# TFTBR.net
KiCad netlist of a schematic drawn in EAGLE
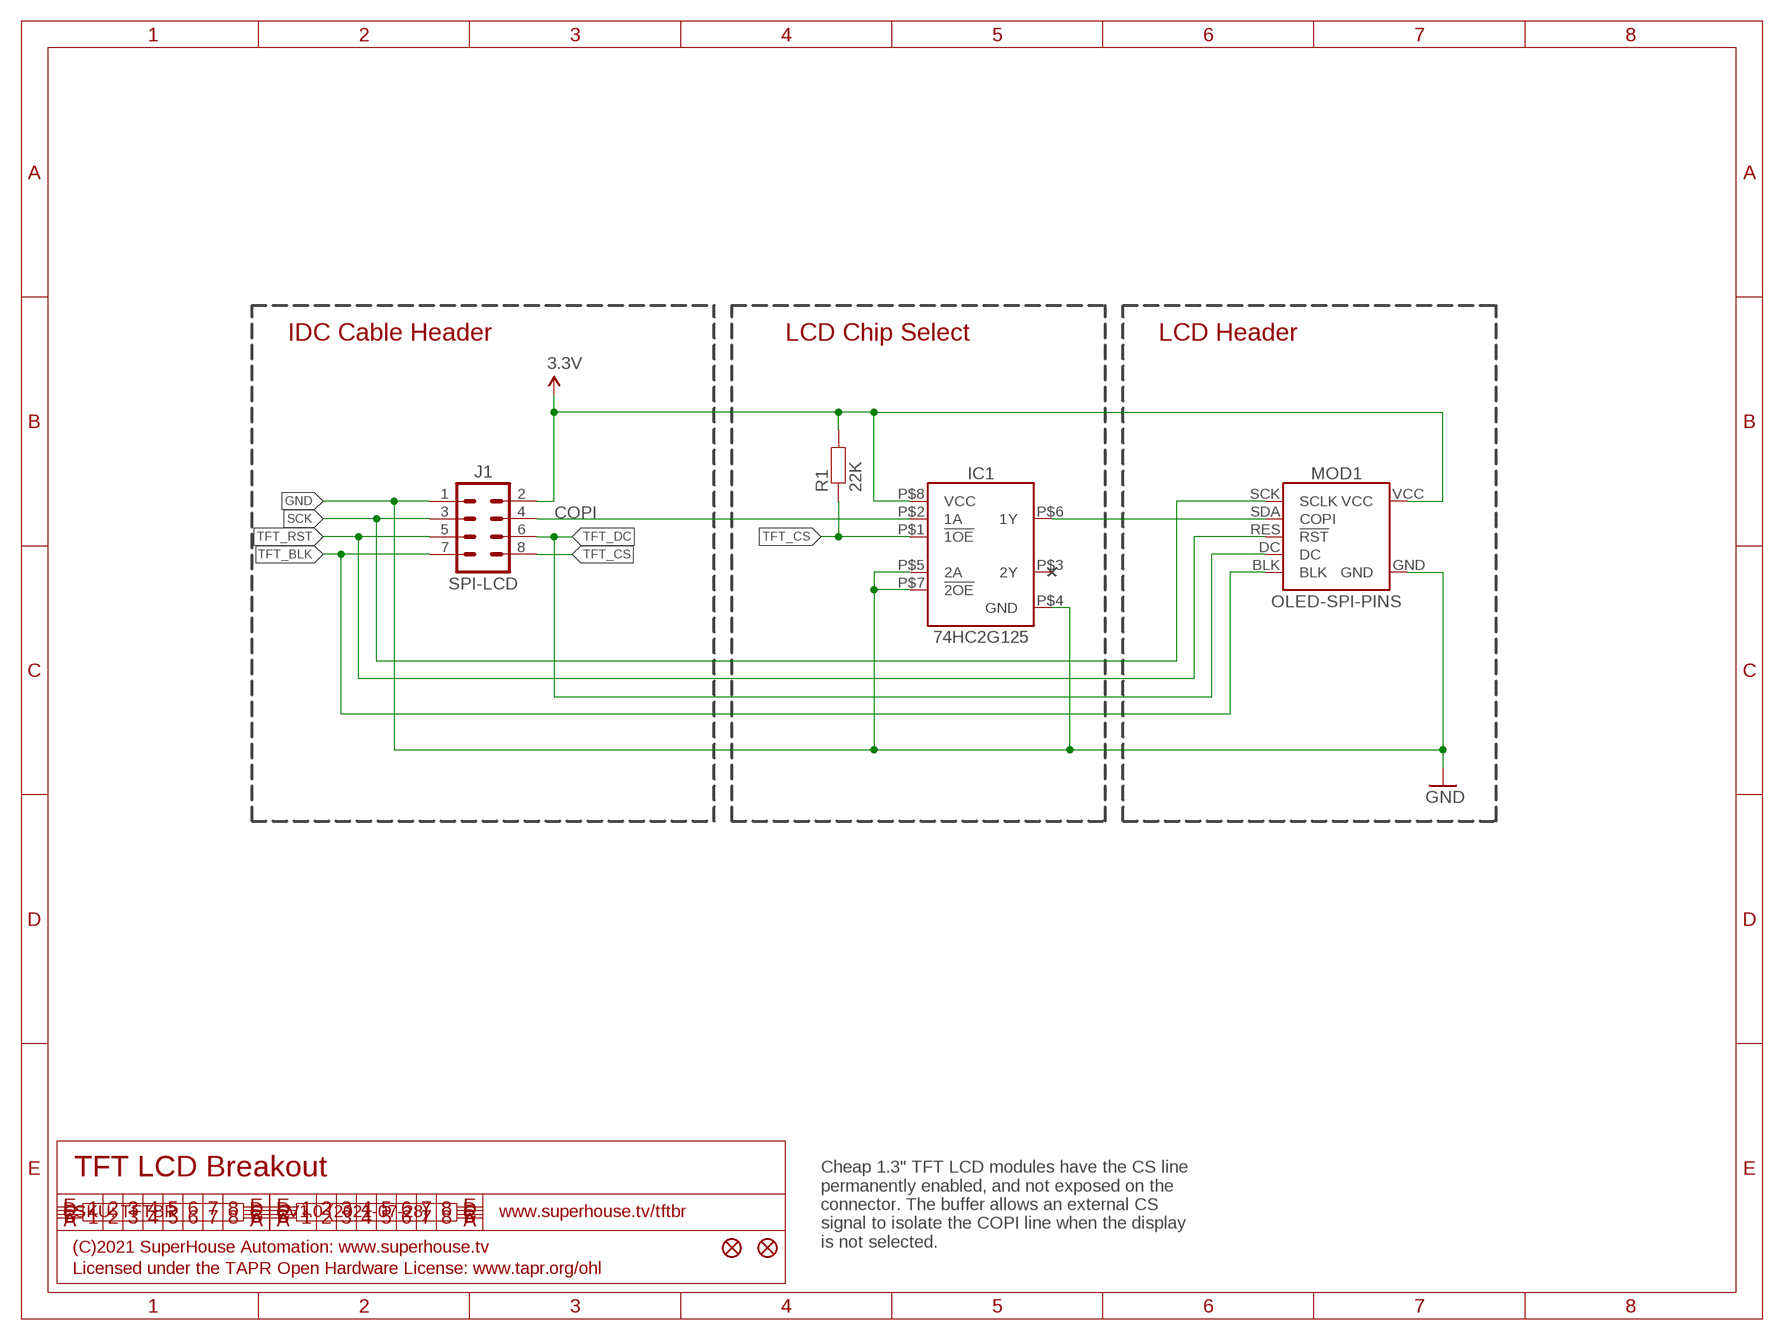
[diagram p0: schematic, sheet 1]

(export (version "E")
  (design (tool "Eeschema 10.0.6"))
  (components
    (comp (ref "FID1")
      (value "FIDUCIAL1X2.5")
      (footprint "eagle-import:FIDUCIAL-1X2.5")
      (libsource (lib "eagle-import") (part "FIDUCIAL1X2.5"))
    )
    (comp (ref "FID2")
      (value "FIDUCIAL1X2.5")
      (footprint "eagle-import:FIDUCIAL-1X2.5")
      (libsource (lib "eagle-import") (part "FIDUCIAL1X2.5"))
    )
    (comp (ref "IC1")
      (value "74HC2G125")
      (footprint "eagle-import:74HC2G125")
      (libsource (lib "eagle-import") (part "74HC2G125-TSSOP8"))
    )
    (comp (ref "J1")
      (value "SPI-LCD")
      (footprint "eagle-import:2X04-2.54-SHROUDED")
      (libsource (lib "eagle-import") (part "M02X4-SHROUD"))
    )
    (comp (ref "MOD1")
      (value "OLED-SPI-PINS")
      (footprint "eagle-import:OLED-240X240-1.3")
      (libsource (lib "eagle-import") (part "OLED-SPI-PINS"))
    )
    (comp (ref "R1")
      (value "22K")
      (footprint "eagle-import:R0603")
      (libsource (lib "eagle-import") (part "RESISTOR0603"))
    )
  )
  (nets
    (net (code "1") (name "/COPI") (class "Default")
      (node (ref "IC1") (pin "P$2") (pinfunction "1A_P$2") (pintype "bidirectional"))
      (node (ref "J1") (pin "4") (pinfunction "4_4") (pintype "passive"))
    )
    (net (code "2") (name "3.3V") (class "Default")
      (node (ref "IC1") (pin "P$8") (pinfunction "VCC_P$8") (pintype "bidirectional"))
      (node (ref "J1") (pin "2") (pinfunction "2_2") (pintype "passive"))
      (node (ref "MOD1") (pin "VCC") (pinfunction "VCC_VCC") (pintype "bidirectional"))
      (node (ref "R1") (pin "2") (pinfunction "2_2") (pintype "passive"))
    )
    (net (code "3") (name "GND") (class "Default")
      (node (ref "IC1") (pin "P$4") (pinfunction "GND_P$4") (pintype "bidirectional"))
      (node (ref "IC1") (pin "P$5") (pinfunction "2A_P$5") (pintype "bidirectional"))
      (node (ref "IC1") (pin "P$7") (pinfunction "~{2OE}_P$7") (pintype "bidirectional"))
      (node (ref "J1") (pin "1") (pinfunction "1_1") (pintype "passive"))
      (node (ref "MOD1") (pin "GND") (pinfunction "GND_GND") (pintype "bidirectional"))
    )
    (net (code "4") (name "Net-(IC1-1Y)") (class "Default")
      (node (ref "IC1") (pin "P$6") (pinfunction "1Y_P$6") (pintype "bidirectional"))
      (node (ref "MOD1") (pin "SDA") (pinfunction "COPI_SDA") (pintype "bidirectional"))
    )
    (net (code "5") (name "SCK") (class "Default")
      (node (ref "J1") (pin "3") (pinfunction "3_3") (pintype "passive"))
      (node (ref "MOD1") (pin "SCK") (pinfunction "SCLK_SCK") (pintype "bidirectional"))
    )
    (net (code "6") (name "TFT_BLK") (class "Default")
      (node (ref "J1") (pin "7") (pinfunction "7_7") (pintype "passive"))
      (node (ref "MOD1") (pin "BLK") (pinfunction "BLK_BLK") (pintype "bidirectional"))
    )
    (net (code "7") (name "TFT_CS") (class "Default")
      (node (ref "IC1") (pin "P$1") (pinfunction "~{1OE}_P$1") (pintype "bidirectional"))
      (node (ref "J1") (pin "8") (pinfunction "8_8") (pintype "passive"))
      (node (ref "R1") (pin "1") (pinfunction "1_1") (pintype "passive"))
    )
    (net (code "8") (name "TFT_DC") (class "Default")
      (node (ref "J1") (pin "6") (pinfunction "6_6") (pintype "passive"))
      (node (ref "MOD1") (pin "DC") (pinfunction "DC_DC") (pintype "bidirectional"))
    )
    (net (code "9") (name "TFT_RST") (class "Default")
      (node (ref "J1") (pin "5") (pinfunction "5_5") (pintype "passive"))
      (node (ref "MOD1") (pin "RES") (pinfunction "~{RST}_RES") (pintype "bidirectional"))
    )
    (net (code "10") (name "unconnected-(IC1-2Y-PadP$3)") (class "Default")
      (node (ref "IC1") (pin "P$3") (pinfunction "2Y_P$3") (pintype "bidirectional"))
    )
  )
)
